# Power.net
KiCad netlist of a schematic drawn in Altium Designer
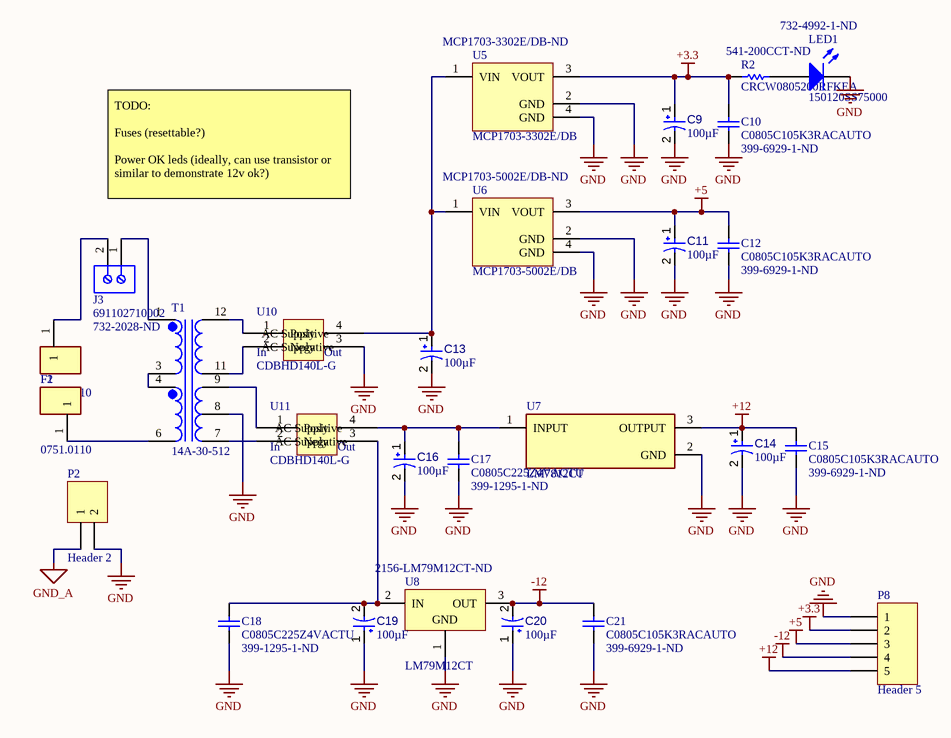
[diagram p0: Power.SchDoc]

(export (version "E")
  (design (tool "Eeschema 10.0.6"))
  (components
    (comp (ref "C9")
      (value "100µF")
      (footprint "CAPPR65-500-1600X1000X1700")
      (description "Aluminum Electrolytic Capacitor, 100 uF, +/- 20%, 100 V, -40 to 85 degC, 2-Pin THD, RoHS, Bulk")
      (fields (field (name "MANUFACTURER") "Panasonic") (field (name "TOLERANCE") "20%"))
      (libsource (lib "") (part "CAP-P-2_1"))
    )
    (comp (ref "C10")
      (value "C0805C105K3RACAUTO")
      (footprint "CAPC2013X140X50ML20T25")
      (fields
        (field (name "MANUFACTURER") "Kemet")
        (field (name "SUPPLIER PART NUMBER 1") "399-6929-1-ND")
        (field (name "TOLERANCE") "10%")
      )
      (libsource (lib "Altium Content Vault") (part "CAP"))
    )
    (comp (ref "C11")
      (value "100µF")
      (footprint "CAPPR65-500-1600X1000X1700")
      (description "Aluminum Electrolytic Capacitor, 100 uF, +/- 20%, 100 V, -40 to 85 degC, 2-Pin THD, RoHS, Bulk")
      (fields (field (name "MANUFACTURER") "Panasonic") (field (name "TOLERANCE") "20%"))
      (libsource (lib "") (part "CAP-P-2_1"))
    )
    (comp (ref "C12")
      (value "C0805C105K3RACAUTO")
      (footprint "CAPC2013X140X50ML20T25")
      (fields
        (field (name "MANUFACTURER") "Kemet")
        (field (name "SUPPLIER PART NUMBER 1") "399-6929-1-ND")
        (field (name "TOLERANCE") "10%")
      )
      (libsource (lib "Altium Content Vault") (part "CAP"))
    )
    (comp (ref "C13")
      (value "100µF")
      (footprint "CAPPR65-500-1600X1000X1700")
      (description "Aluminum Electrolytic Capacitor, 100 uF, +/- 20%, 100 V, -40 to 85 degC, 2-Pin THD, RoHS, Bulk")
      (fields (field (name "MANUFACTURER") "Panasonic") (field (name "TOLERANCE") "20%"))
      (libsource (lib "") (part "CAP-P-2_1"))
    )
    (comp (ref "C14")
      (value "100µF")
      (footprint "CAPPR65-500-1600X1000X1700")
      (description "Aluminum Electrolytic Capacitor, 100 uF, +/- 20%, 100 V, -40 to 85 degC, 2-Pin THD, RoHS, Bulk")
      (fields (field (name "MANUFACTURER") "Panasonic") (field (name "TOLERANCE") "20%"))
      (libsource (lib "") (part "CAP-P-2_1"))
    )
    (comp (ref "C15")
      (value "C0805C105K3RACAUTO")
      (footprint "CAPC2013X140X50ML20T25")
      (fields
        (field (name "MANUFACTURER") "Kemet")
        (field (name "SUPPLIER PART NUMBER 1") "399-6929-1-ND")
        (field (name "TOLERANCE") "10%")
      )
      (libsource (lib "Altium Content Vault") (part "CAP"))
    )
    (comp (ref "C16")
      (value "100µF")
      (footprint "CAPPR65-500-1600X1000X1700")
      (description "Aluminum Electrolytic Capacitor, 100 uF, +/- 20%, 100 V, -40 to 85 degC, 2-Pin THD, RoHS, Bulk")
      (fields (field (name "MANUFACTURER") "Panasonic") (field (name "TOLERANCE") "20%"))
      (libsource (lib "") (part "CAP-P-2_1"))
    )
    (comp (ref "C17")
      (value "C0805C225Z4VACTU")
      (footprint "CAPC2013X100X50NL20T25")
      (fields
        (field (name "MANUFACTURER") "Kemet")
        (field (name "SUPPLIER PART NUMBER 1") "399-1295-1-ND")
        (field (name "TOLERANCE") "80%")
        (field (name "VOLTAGE") "16V")
      )
      (libsource (lib "Altium Content Vault") (part "CAP"))
    )
    (comp (ref "C18")
      (value "C0805C225Z4VACTU")
      (footprint "CAPC2013X100X50NL20T25")
      (fields
        (field (name "MANUFACTURER") "Kemet")
        (field (name "SUPPLIER PART NUMBER 1") "399-1295-1-ND")
        (field (name "TOLERANCE") "80%")
        (field (name "VOLTAGE") "16V")
      )
      (libsource (lib "Altium Content Vault") (part "CAP"))
    )
    (comp (ref "C19")
      (value "100µF")
      (footprint "CAPPR65-500-1600X1000X1700")
      (description "Aluminum Electrolytic Capacitor, 100 uF, +/- 20%, 100 V, -40 to 85 degC, 2-Pin THD, RoHS, Bulk")
      (fields (field (name "MANUFACTURER") "Panasonic") (field (name "TOLERANCE") "20%"))
      (libsource (lib "Deakin University- School of Engineering") (part "CAP-P-2"))
    )
    (comp (ref "C20")
      (value "100µF")
      (footprint "CAPPR65-500-1600X1000X1700")
      (description "Aluminum Electrolytic Capacitor, 100 uF, +/- 20%, 100 V, -40 to 85 degC, 2-Pin THD, RoHS, Bulk")
      (fields (field (name "MANUFACTURER") "Panasonic") (field (name "TOLERANCE") "20%"))
      (libsource (lib "Deakin University- School of Engineering") (part "CAP-P-2"))
    )
    (comp (ref "C21")
      (value "C0805C105K3RACAUTO")
      (footprint "CAPC2013X140X50ML20T25")
      (fields
        (field (name "MANUFACTURER") "Kemet")
        (field (name "SUPPLIER PART NUMBER 1") "399-6929-1-ND")
        (field (name "TOLERANCE") "10%")
      )
      (libsource (lib "Altium Content Vault") (part "CAP"))
    )
    (comp (ref "F1")
      (value "0751.0110")
      (footprint "FP-0751_0110-MFG")
      (description "FUSE CLIP CARTRIDGE 10A PCB")
      (fields
        (field (name "OCTOPART") "https://octopart.com/0751.0110-schurter-19402")
        (field (name "MANUFACTURER") "Schurter")
      )
      (libsource (lib "") (part "6594cd1380bf084bed0a40489f8b218_1"))
    )
    (comp (ref "F2")
      (value "0751.0110")
      (footprint "FP-0751_0110-MFG")
      (description "FUSE CLIP CARTRIDGE 10A PCB")
      (fields
        (field (name "OCTOPART") "https://octopart.com/0751.0110-schurter-19402")
        (field (name "MANUFACTURER") "Schurter")
      )
      (libsource (lib "Altium Content Vault") (part "6594cd1380bf084bed0a40489f8b218"))
    )
    (comp (ref "J3")
      (value "691102710002")
      (footprint "691102710002")
      (description "Series 102 - 5.00 mm Horizontal Entry Modular with Pressure Clamp WR-TBL, 2 pin")
      (fields
        (field (name "MANUFACTURER") "Wurth Elektronik")
        (field (name "SUPPLIER PART NUMBER 1") "732-2028-ND")
        (field (name "VOLTAGE") "300V")
        (field (name "PUBLISHER") "WurthElektronik")
      )
      (libsource (lib "Altium Content Vault") (part "WE-CN-1P-F-TB2"))
    )
    (comp (ref "LED1")
      (value "150120SS75000")
      (footprint "1206_A")
      (description "SMD mono-color Chip LED, WL-SMCW, Super Red")
      (fields
        (field (name "MANUFACTURER") "Wuerth Elektronik")
        (field (name "SUPPLIER PART NUMBER 1") "732-4992-1-ND")
      )
      (libsource (lib "Altium Content Vault") (part "WE-LED_K1A2-2"))
    )
    (comp (ref "P2")
      (value "Header 2")
      (footprint "HDR1X2")
      (description "Header, 2-Pin")
      (fields (field (name "PUBLISHER") "Altium Limited"))
      (libsource (lib "Miscellaneous Connectors") (part "Header 2"))
    )
    (comp (ref "P8")
      (value "Header 5")
      (footprint "HDR1X5")
      (description "Header, 5-Pin")
      (fields (field (name "PUBLISHER") "Altium Limited"))
      (libsource (lib "Miscellaneous Connectors") (part "Header 5"))
    )
    (comp (ref "R2")
      (value "CRCW0805200RFKEA")
      (footprint "RESC2013X50X30NL20T20")
      (fields
        (field (name "MANUFACTURER") "Vishay Dale")
        (field (name "SUPPLIER PART NUMBER 1") "541-200CCT-ND")
        (field (name "TOLERANCE") "1%")
      )
      (libsource (lib "Altium Content Vault") (part "RES"))
    )
    (comp (ref "T1")
      (value "14A-30-512")
      (footprint "XFMR_14A-30-512")
      (description "International One-4-All Triple Output Transformer")
      (libsource (lib "SnapEDA_Library") (part "14A-30-512"))
    )
    (comp (ref "U5")
      (value "MCP1703-3302E/DB")
      (footprint "SOT-223-DB3_M")
      (description "250 mA, 16V, Low Quiescent Current LDO Regulator, 3-Pin SOT-223, Extended Temperature")
      (fields
        (field (name "SUPPLIER PART NUMBER 1") "MCP1703-3302E/DB-ND")
        (field (name "MANUFACTURER") "Microchip")
      )
      (libsource (lib "Altium Content Vault") (part "PM-LINEREG-MCP1703-IL4"))
    )
    (comp (ref "U6")
      (value "MCP1703-5002E/DB")
      (footprint "SOT-223-DB3_N")
      (description "250 mA, 16V, Low Quiescent Current LDO Regulator, 3-Pin SOT-223, Extended Temperature")
      (fields
        (field (name "SUPPLIER PART NUMBER 1") "MCP1703-5002E/DB-ND")
        (field (name "MANUFACTURER") "Microchip")
      )
      (libsource (lib "Altium Content Vault") (part "PM-LINEREG-MCP1703-IL4"))
    )
    (comp (ref "U7")
      (value "LM7812CT")
      (footprint "FP-TO220B03-MFG")
      (description "IC REG LINEAR 12V 1A TO220-3")
      (fields
        (field (name "OCTOPART") "https://octopart.com/lm7812ct-on+semiconductor-14383031")
        (field (name "OBSOLETE PART") "true")
      )
      (libsource (lib "Altium Content Vault") (part "6207a8f1a6b4db326a9e0a8a99b4969"))
    )
    (comp (ref "U8")
      (value "LM79M12CT")
      (footprint "NDE0003A")
      (description "3-Terminal Negative Regulators, 3-pin TO-220")
      (fields
        (field (name "MANUFACTURER") "Texas Instruments")
        (field (name "SUPPLIER PART NUMBER 1") "2156-LM79M12CT-ND")
      )
      (libsource (lib "Altium Content Vault") (part "PM-REG-LM7905-SIL3"))
    )
    (comp (ref "U10")
      (value "CDBHD140L-G")
      (footprint "SOP270P700X290-4N")
      (description "DIODE SCHOTTKY 1A 40V TO-269AA")
      (libsource (lib "Deakin University- School of Engineering") (part "CDBHD140L-G"))
    )
    (comp (ref "U11")
      (value "CDBHD140L-G")
      (footprint "SOP270P700X290-4N")
      (description "DIODE SCHOTTKY 1A 40V TO-269AA")
      (libsource (lib "Deakin University- School of Engineering") (part "CDBHD140L-G"))
    )
  )
  (nets
    (net (code "1") (name "+3.3") (class "Default")
      (node (ref "C10") (pin "2") (pinfunction "2_2") (pintype "passive"))
      (node (ref "C9") (pin "1") (pinfunction "1_1") (pintype "passive"))
      (node (ref "P8") (pin "2") (pinfunction "2_2") (pintype "passive"))
      (node (ref "R2") (pin "1") (pinfunction "1_1") (pintype "passive"))
      (node (ref "U5") (pin "3") (pinfunction "VOUT_3") (pintype "power_in"))
    )
    (net (code "2") (name "+5") (class "Default")
      (node (ref "C11") (pin "1") (pinfunction "1_1") (pintype "passive"))
      (node (ref "C12") (pin "2") (pinfunction "2_2") (pintype "passive"))
      (node (ref "P8") (pin "3") (pinfunction "3_3") (pintype "passive"))
      (node (ref "U6") (pin "3") (pinfunction "VOUT_3") (pintype "power_in"))
    )
    (net (code "3") (name "+12") (class "Default")
      (node (ref "C14") (pin "1") (pinfunction "1_1") (pintype "passive"))
      (node (ref "C15") (pin "2") (pinfunction "2_2") (pintype "passive"))
      (node (ref "P8") (pin "5") (pinfunction "5_5") (pintype "passive"))
      (node (ref "U7") (pin "3") (pinfunction "OUTPUT_3") (pintype "power_in"))
    )
    (net (code "4") (name "-12") (class "Default")
      (node (ref "C20") (pin "2") (pinfunction "2_2") (pintype "passive"))
      (node (ref "C21") (pin "2") (pinfunction "2_2") (pintype "passive"))
      (node (ref "P8") (pin "4") (pinfunction "4_4") (pintype "passive"))
      (node (ref "U8") (pin "3") (pinfunction "OUT_3") (pintype "power_in"))
    )
    (net (code "5") (name "GND") (class "Default")
      (node (ref "C10") (pin "1") (pinfunction "1_1") (pintype "passive"))
      (node (ref "C11") (pin "2") (pinfunction "2_2") (pintype "passive"))
      (node (ref "C12") (pin "1") (pinfunction "1_1") (pintype "passive"))
      (node (ref "C13") (pin "2") (pinfunction "2_2") (pintype "passive"))
      (node (ref "C14") (pin "2") (pinfunction "2_2") (pintype "passive"))
      (node (ref "C15") (pin "1") (pinfunction "1_1") (pintype "passive"))
      (node (ref "C16") (pin "2") (pinfunction "2_2") (pintype "passive"))
      (node (ref "C17") (pin "1") (pinfunction "1_1") (pintype "passive"))
      (node (ref "C18") (pin "1") (pinfunction "1_1") (pintype "passive"))
      (node (ref "C19") (pin "1") (pinfunction "1_1") (pintype "passive"))
      (node (ref "C20") (pin "1") (pinfunction "1_1") (pintype "passive"))
      (node (ref "C21") (pin "1") (pinfunction "1_1") (pintype "passive"))
      (node (ref "C9") (pin "2") (pinfunction "2_2") (pintype "passive"))
      (node (ref "LED1") (pin "1") (pinfunction "K_1") (pintype "passive"))
      (node (ref "P2") (pin "2") (pinfunction "2_2") (pintype "passive"))
      (node (ref "P8") (pin "1") (pinfunction "1_1") (pintype "passive"))
      (node (ref "T1") (pin "8") (pinfunction "8_8") (pintype "passive"))
      (node (ref "U10") (pin "3") (pinfunction "AC_Supply_3") (pintype "power_in"))
      (node (ref "U5") (pin "2") (pinfunction "GND_2") (pintype "power_in"))
      (node (ref "U5") (pin "4") (pinfunction "GND_4") (pintype "power_in"))
      (node (ref "U6") (pin "2") (pinfunction "GND_2") (pintype "power_in"))
      (node (ref "U6") (pin "4") (pinfunction "GND_4") (pintype "power_in"))
      (node (ref "U7") (pin "2") (pinfunction "GND_2") (pintype "power_in"))
      (node (ref "U8") (pin "1") (pinfunction "GND_1") (pintype "power_in"))
    )
    (net (code "6") (name "GND_A") (class "Default")
      (node (ref "P2") (pin "1") (pinfunction "1_1") (pintype "passive"))
    )
    (net (code "7") (name "Net-(F1-Pad1)") (class "Default")
      (node (ref "F1") (pin "1") (pinfunction "1_1") (pintype "passive"))
      (node (ref "T1") (pin "6") (pinfunction "6_6") (pintype "passive"))
    )
    (net (code "8") (name "Net-(F2-Pad1)") (class "Default")
      (node (ref "F2") (pin "1") (pinfunction "1_1") (pintype "passive"))
      (node (ref "J3") (pin "2") (pinfunction "2_2") (pintype "passive"))
    )
    (net (code "9") (name "Net-(J3-Pad1)") (class "Default")
      (node (ref "J3") (pin "1") (pinfunction "1_1") (pintype "passive"))
      (node (ref "T1") (pin "1") (pinfunction "1_1") (pintype "passive"))
    )
    (net (code "10") (name "Net-(LED1-A)") (class "Default")
      (node (ref "LED1") (pin "2") (pinfunction "A_2") (pintype "passive"))
      (node (ref "R2") (pin "2") (pinfunction "2_2") (pintype "passive"))
    )
    (net (code "11") (name "Net-(T1-Pad3)") (class "Default")
      (node (ref "T1") (pin "3") (pinfunction "3_3") (pintype "passive"))
      (node (ref "T1") (pin "4") (pinfunction "4_4") (pintype "passive"))
    )
    (net (code "12") (name "Net-(U5-VIN)") (class "Default")
      (node (ref "C13") (pin "1") (pinfunction "1_1") (pintype "passive"))
      (node (ref "U10") (pin "4") (pinfunction "AC_Supply_4") (pintype "power_in"))
      (node (ref "U5") (pin "1") (pinfunction "VIN_1") (pintype "power_in"))
      (node (ref "U6") (pin "1") (pinfunction "VIN_1") (pintype "power_in"))
    )
    (net (code "13") (name "Net-(U7-INPUT)") (class "Default")
      (node (ref "C16") (pin "1") (pinfunction "1_1") (pintype "passive"))
      (node (ref "C17") (pin "2") (pinfunction "2_2") (pintype "passive"))
      (node (ref "U11") (pin "4") (pinfunction "AC_Supply_4") (pintype "power_in"))
      (node (ref "U7") (pin "1") (pinfunction "INPUT_1") (pintype "power_in"))
    )
    (net (code "14") (name "Net-(U8-IN)") (class "Default")
      (node (ref "C18") (pin "2") (pinfunction "2_2") (pintype "passive"))
      (node (ref "C19") (pin "2") (pinfunction "2_2") (pintype "passive"))
      (node (ref "U11") (pin "3") (pinfunction "AC_Supply_3") (pintype "power_in"))
      (node (ref "U8") (pin "2") (pinfunction "IN_2") (pintype "power_in"))
    )
    (net (code "15") (name "Net-(U10-Negative)") (class "Default")
      (node (ref "T1") (pin "11") (pinfunction "11_11") (pintype "passive"))
      (node (ref "U10") (pin "2") (pinfunction "Negative_2") (pintype "power_in"))
    )
    (net (code "16") (name "Net-(U10-Positive)") (class "Default")
      (node (ref "T1") (pin "12") (pinfunction "12_12") (pintype "passive"))
      (node (ref "U10") (pin "1") (pinfunction "Positive_1") (pintype "power_in"))
    )
    (net (code "17") (name "Net-(U11-Negative)") (class "Default")
      (node (ref "T1") (pin "7") (pinfunction "7_7") (pintype "passive"))
      (node (ref "U11") (pin "2") (pinfunction "Negative_2") (pintype "power_in"))
    )
    (net (code "18") (name "Net-(U11-Positive)") (class "Default")
      (node (ref "T1") (pin "9") (pinfunction "9_9") (pintype "passive"))
      (node (ref "U11") (pin "1") (pinfunction "Positive_1") (pintype "power_in"))
    )
  )
)
